# Sheet1.net
KiCad netlist of a schematic drawn in Altium Designer
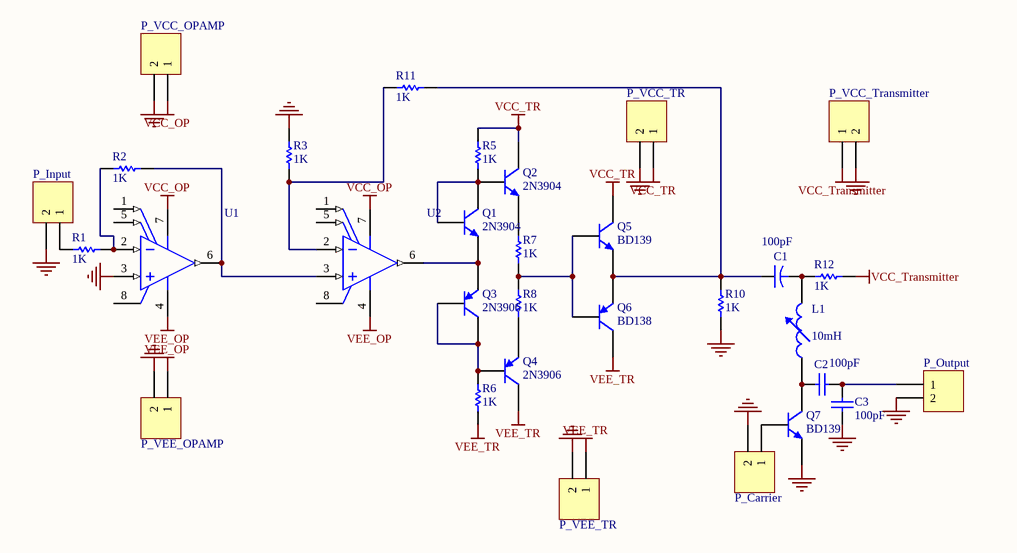
[diagram p0: Sheet1.SchDoc]

(export (version "E")
  (design (tool "Eeschema 10.0.6"))
  (components
    (comp (ref "C1")
      (value "100pF")
      (footprint "CAPR5-4X5")
      (description "Capacitor")
      (fields (field (name "Comment") "Cap2") (field (name "PUBLISHER") "Altium Limited"))
      (libsource (lib "Miscellaneous Devices") (part "Cap2"))
    )
    (comp (ref "C2")
      (value "100pF")
      (footprint "RAD-0.3")
      (description "Capacitor")
      (fields (field (name "Comment") "Cap") (field (name "PUBLISHER") "Altium Limited"))
      (libsource (lib "Miscellaneous Devices") (part "Cap"))
    )
    (comp (ref "C3")
      (value "100pF")
      (footprint "RAD-0.3")
      (description "Capacitor")
      (fields (field (name "Comment") "Cap") (field (name "PUBLISHER") "Altium Limited"))
      (libsource (lib "Miscellaneous Devices") (part "Cap"))
    )
    (comp (ref "L1")
      (value "10mH")
      (footprint "AXIAL-0.8")
      (description "Adjustable Inductor")
      (fields (field (name "Comment") "Inductor Adj") (field (name "PUBLISHER") "Altium Limited"))
      (libsource (lib "Miscellaneous Devices") (part "Inductor Adj"))
    )
    (comp (ref "P_Carrier")
      (value "Header 2")
      (footprint "HDR1X2")
      (description "Header, 2-Pin")
      (fields (field (name "PUBLISHER") "Altium Limited"))
      (libsource (lib "") (part "Header 2_1"))
    )
    (comp (ref "P_Input")
      (value "Header 2")
      (footprint "HDR1X2")
      (description "Header, 2-Pin")
      (fields (field (name "PUBLISHER") "Altium Limited"))
      (libsource (lib "Miscellaneous Connectors") (part "Header 2"))
    )
    (comp (ref "P_Output")
      (value "Header 2")
      (footprint "HDR1X2")
      (description "Header, 2-Pin")
      (fields (field (name "PUBLISHER") "Altium Limited"))
      (libsource (lib "Miscellaneous Connectors") (part "Header 2"))
    )
    (comp (ref "P_VCC_OPAMP")
      (value "Header 2")
      (footprint "HDR1X2")
      (description "Header, 2-Pin")
      (fields (field (name "PUBLISHER") "Altium Limited"))
      (libsource (lib "Miscellaneous Connectors") (part "Header 2"))
    )
    (comp (ref "P_VCC_TR")
      (value "Header 2")
      (footprint "HDR1X2")
      (description "Header, 2-Pin")
      (fields (field (name "PUBLISHER") "Altium Limited"))
      (libsource (lib "Miscellaneous Connectors") (part "Header 2"))
    )
    (comp (ref "P_VCC_Transmitter")
      (value "Header 2")
      (footprint "HDR1X2")
      (description "Header, 2-Pin")
      (fields (field (name "PUBLISHER") "Altium Limited"))
      (libsource (lib "") (part "Header 2_2"))
    )
    (comp (ref "P_VEE_OPAMP")
      (value "Header 2")
      (footprint "HDR1X2")
      (description "Header, 2-Pin")
      (fields (field (name "PUBLISHER") "Altium Limited"))
      (libsource (lib "") (part "Header 2_1"))
    )
    (comp (ref "P_VEE_TR")
      (value "Header 2")
      (footprint "HDR1X2")
      (description "Header, 2-Pin")
      (fields (field (name "PUBLISHER") "Altium Limited"))
      (libsource (lib "") (part "Header 2_1"))
    )
    (comp (ref "Q1")
      (value "2N3904")
      (footprint "TO-92A")
      (description "NPN General Purpose Amplifier")
      (fields (field (name "PUBLISHER") "Altium Limited"))
      (libsource (lib "Miscellaneous Devices") (part "2N3904"))
    )
    (comp (ref "Q2")
      (value "2N3904")
      (footprint "TO-92A")
      (description "NPN General Purpose Amplifier")
      (fields (field (name "PUBLISHER") "Altium Limited"))
      (libsource (lib "Miscellaneous Devices") (part "2N3904"))
    )
    (comp (ref "Q3")
      (value "2N3906")
      (footprint "TO-92A")
      (description "PNP General Purpose Amplifier")
      (fields (field (name "PUBLISHER") "Altium Limited"))
      (libsource (lib "Miscellaneous Devices") (part "2N3906"))
    )
    (comp (ref "Q4")
      (value "2N3906")
      (footprint "TO-92A")
      (description "PNP General Purpose Amplifier")
      (fields (field (name "PUBLISHER") "Altium Limited"))
      (libsource (lib "Miscellaneous Devices") (part "2N3906"))
    )
    (comp (ref "Q5")
      (value "BD139")
      (footprint "SOT-32")
      (description "NPN Transistor")
      (fields (field (name "E-MAIL") "picpars@gmail.com"))
      (libsource (lib "usefully_Library") (part "BD139"))
    )
    (comp (ref "Q6")
      (value "BD138")
      (footprint "SOT-32")
      (description "PNP Transistor")
      (fields (field (name "E-MAIL") "picpars@gmail.com"))
      (libsource (lib "usefully_Library") (part "BD138"))
    )
    (comp (ref "Q7")
      (value "BD139")
      (footprint "SOT-32")
      (description "NPN Transistor")
      (fields (field (name "E-MAIL") "picpars@gmail.com"))
      (libsource (lib "usefully_Library") (part "BD139"))
    )
    (comp (ref "R1")
      (value "1K")
      (footprint "AXIAL-0.3")
      (description "Resistor")
      (fields (field (name "Comment") "Res1") (field (name "PUBLISHER") "Altium Limited"))
      (libsource (lib "Miscellaneous Devices") (part "Res1"))
    )
    (comp (ref "R2")
      (value "1K")
      (footprint "AXIAL-0.3")
      (description "Resistor")
      (fields (field (name "Comment") "Res1") (field (name "PUBLISHER") "Altium Limited"))
      (libsource (lib "Miscellaneous Devices") (part "Res1"))
    )
    (comp (ref "R3")
      (value "1K")
      (footprint "AXIAL-0.3")
      (description "Resistor")
      (fields (field (name "Comment") "Res1") (field (name "PUBLISHER") "Altium Limited"))
      (libsource (lib "Miscellaneous Devices") (part "Res1"))
    )
    (comp (ref "R5")
      (value "1K")
      (footprint "AXIAL-0.3")
      (description "Resistor")
      (fields (field (name "Comment") "Res1") (field (name "PUBLISHER") "Altium Limited"))
      (libsource (lib "Miscellaneous Devices") (part "Res1"))
    )
    (comp (ref "R6")
      (value "1K")
      (footprint "AXIAL-0.3")
      (description "Resistor")
      (fields (field (name "Comment") "Res1") (field (name "PUBLISHER") "Altium Limited"))
      (libsource (lib "Miscellaneous Devices") (part "Res1"))
    )
    (comp (ref "R7")
      (value "1K")
      (footprint "AXIAL-0.3")
      (description "Resistor")
      (fields (field (name "Comment") "Res1") (field (name "PUBLISHER") "Altium Limited"))
      (libsource (lib "Miscellaneous Devices") (part "Res1"))
    )
    (comp (ref "R8")
      (value "1K")
      (footprint "AXIAL-0.3")
      (description "Resistor")
      (fields (field (name "Comment") "Res1") (field (name "PUBLISHER") "Altium Limited"))
      (libsource (lib "Miscellaneous Devices") (part "Res1"))
    )
    (comp (ref "R10")
      (value "1K")
      (footprint "AXIAL-0.3")
      (description "Resistor")
      (fields (field (name "Comment") "Res1") (field (name "PUBLISHER") "Altium Limited"))
      (libsource (lib "Miscellaneous Devices") (part "Res1"))
    )
    (comp (ref "R11")
      (value "1K")
      (footprint "AXIAL-0.3")
      (description "Resistor")
      (fields (field (name "Comment") "Res1") (field (name "PUBLISHER") "Altium Limited"))
      (libsource (lib "Miscellaneous Devices") (part "Res1"))
    )
    (comp (ref "R12")
      (value "1K")
      (footprint "AXIAL-0.3")
      (description "Resistor")
      (fields (field (name "Comment") "Res1") (field (name "PUBLISHER") "Altium Limited"))
      (libsource (lib "Miscellaneous Devices") (part "Res1"))
    )
    (comp (ref "U1")
      (value "UA741CP")
      (footprint "TI-P8")
      (description "General-Purpose Operational Amplifier, 7 to 36 V, 0 to 70 degC, 8-pin DIP (P8), Pb-Free (RoHS)")
      (fields (field (name "MANUFACTURER") "Texas Instruments"))
      (libsource (lib "TI_Amplifiers_and_Linear_Operational (2)") (part "UA741CP"))
    )
    (comp (ref "U2")
      (value "UA741CP")
      (footprint "TI-P8")
      (description "General-Purpose Operational Amplifier, 7 to 36 V, 0 to 70 degC, 8-pin DIP (P8), Pb-Free (RoHS)")
      (fields (field (name "MANUFACTURER") "Texas Instruments"))
      (libsource (lib "TI_Amplifiers_and_Linear_Operational (2)") (part "UA741CP"))
    )
  )
  (nets
    (net (code "1") (name "GND") (class "Default")
      (node (ref "C3") (pin "1") (pinfunction "1_1") (pintype "passive"))
      (node (ref "P_Carrier") (pin "2") (pinfunction "2_2") (pintype "passive"))
      (node (ref "P_Input") (pin "2") (pinfunction "2_2") (pintype "passive"))
      (node (ref "P_Output") (pin "2") (pinfunction "2_2") (pintype "passive"))
      (node (ref "P_VCC_OPAMP") (pin "2") (pinfunction "2_2") (pintype "passive"))
      (node (ref "P_VCC_TR") (pin "2") (pinfunction "2_2") (pintype "passive"))
      (node (ref "P_VCC_Transmitter") (pin "2") (pinfunction "2_2") (pintype "passive"))
      (node (ref "P_VEE_OPAMP") (pin "2") (pinfunction "2_2") (pintype "passive"))
      (node (ref "P_VEE_TR") (pin "2") (pinfunction "2_2") (pintype "passive"))
      (node (ref "Q7") (pin "E") (pinfunction "E_E") (pintype "passive"))
      (node (ref "R10") (pin "1") (pinfunction "1_1") (pintype "passive"))
      (node (ref "R3") (pin "2") (pinfunction "2_2") (pintype "passive"))
      (node (ref "U1") (pin "3") (pinfunction "IN+_3") (pintype "input"))
    )
    (net (code "2") (name "Net-(C1-Pad1)") (class "Default")
      (node (ref "C1") (pin "1") (pinfunction "1_1") (pintype "passive"))
      (node (ref "Q5") (pin "E") (pinfunction "E_E") (pintype "passive"))
      (node (ref "Q6") (pin "E") (pinfunction "E_E") (pintype "passive"))
      (node (ref "R10") (pin "2") (pinfunction "2_2") (pintype "passive"))
      (node (ref "R11") (pin "1") (pinfunction "1_1") (pintype "passive"))
    )
    (net (code "3") (name "Net-(C1-Pad2)") (class "Default")
      (node (ref "C1") (pin "2") (pinfunction "2_2") (pintype "passive"))
      (node (ref "L1") (pin "2") (pinfunction "2_2") (pintype "passive"))
      (node (ref "R12") (pin "2") (pinfunction "2_2") (pintype "passive"))
    )
    (net (code "4") (name "Net-(C2-Pad1)") (class "Default")
      (node (ref "C2") (pin "1") (pinfunction "1_1") (pintype "passive"))
      (node (ref "L1") (pin "1") (pinfunction "1_1") (pintype "passive"))
      (node (ref "Q7") (pin "C") (pinfunction "C_C") (pintype "passive"))
    )
    (net (code "5") (name "Net-(C2-Pad2)") (class "Default")
      (node (ref "C2") (pin "2") (pinfunction "2_2") (pintype "passive"))
      (node (ref "C3") (pin "2") (pinfunction "2_2") (pintype "passive"))
      (node (ref "P_Output") (pin "1") (pinfunction "1_1") (pintype "passive"))
    )
    (net (code "6") (name "Net-(P_Carrier-Pad1)") (class "Default")
      (node (ref "P_Carrier") (pin "1") (pinfunction "1_1") (pintype "passive"))
      (node (ref "Q7") (pin "B") (pinfunction "B_B") (pintype "passive"))
    )
    (net (code "7") (name "Net-(P_Input-Pad1)") (class "Default")
      (node (ref "P_Input") (pin "1") (pinfunction "1_1") (pintype "passive"))
      (node (ref "R1") (pin "2") (pinfunction "2_2") (pintype "passive"))
    )
    (net (code "8") (name "Net-(Q1-B)") (class "Default")
      (node (ref "Q1") (pin "2") (pinfunction "B_2") (pintype "passive"))
      (node (ref "Q1") (pin "3") (pinfunction "C_3") (pintype "passive"))
      (node (ref "Q2") (pin "2") (pinfunction "B_2") (pintype "passive"))
      (node (ref "R5") (pin "1") (pinfunction "1_1") (pintype "passive"))
    )
    (net (code "9") (name "Net-(Q1-E)") (class "Default")
      (node (ref "Q1") (pin "1") (pinfunction "E_1") (pintype "passive"))
      (node (ref "Q3") (pin "1") (pinfunction "E_1") (pintype "passive"))
      (node (ref "U2") (pin "6") (pinfunction "OUT_6") (pintype "output"))
    )
    (net (code "10") (name "Net-(Q2-E)") (class "Default")
      (node (ref "Q2") (pin "1") (pinfunction "E_1") (pintype "passive"))
      (node (ref "R7") (pin "2") (pinfunction "2_2") (pintype "passive"))
    )
    (net (code "11") (name "Net-(Q3-B)") (class "Default")
      (node (ref "Q3") (pin "2") (pinfunction "B_2") (pintype "passive"))
      (node (ref "Q3") (pin "3") (pinfunction "C_3") (pintype "passive"))
      (node (ref "Q4") (pin "2") (pinfunction "B_2") (pintype "passive"))
      (node (ref "R6") (pin "2") (pinfunction "2_2") (pintype "passive"))
    )
    (net (code "12") (name "Net-(Q4-E)") (class "Default")
      (node (ref "Q4") (pin "1") (pinfunction "E_1") (pintype "passive"))
      (node (ref "R8") (pin "1") (pinfunction "1_1") (pintype "passive"))
    )
    (net (code "13") (name "Net-(Q5-PadB)") (class "Default")
      (node (ref "Q5") (pin "B") (pinfunction "B_B") (pintype "passive"))
      (node (ref "Q6") (pin "B") (pinfunction "B_B") (pintype "passive"))
      (node (ref "R7") (pin "1") (pinfunction "1_1") (pintype "passive"))
      (node (ref "R8") (pin "2") (pinfunction "2_2") (pintype "passive"))
    )
    (net (code "14") (name "Net-(U1-IN-)") (class "Default")
      (node (ref "R1") (pin "1") (pinfunction "1_1") (pintype "passive"))
      (node (ref "R2") (pin "1") (pinfunction "1_1") (pintype "passive"))
      (node (ref "U1") (pin "2") (pinfunction "IN-_2") (pintype "input"))
    )
    (net (code "15") (name "Net-(U1-OUT)") (class "Default")
      (node (ref "R2") (pin "2") (pinfunction "2_2") (pintype "passive"))
      (node (ref "U1") (pin "6") (pinfunction "OUT_6") (pintype "output"))
      (node (ref "U2") (pin "3") (pinfunction "IN+_3") (pintype "input"))
    )
    (net (code "16") (name "Net-(U2-IN-)") (class "Default")
      (node (ref "R11") (pin "2") (pinfunction "2_2") (pintype "passive"))
      (node (ref "R3") (pin "1") (pinfunction "1_1") (pintype "passive"))
      (node (ref "U2") (pin "2") (pinfunction "IN-_2") (pintype "input"))
    )
    (net (code "17") (name "VCC_OP") (class "Default")
      (node (ref "P_VCC_OPAMP") (pin "1") (pinfunction "1_1") (pintype "passive"))
      (node (ref "U1") (pin "7") (pinfunction "VCC+_7") (pintype "power_in"))
      (node (ref "U2") (pin "7") (pinfunction "VCC+_7") (pintype "power_in"))
    )
    (net (code "18") (name "VCC_TR") (class "Default")
      (node (ref "P_VCC_TR") (pin "1") (pinfunction "1_1") (pintype "passive"))
      (node (ref "Q2") (pin "3") (pinfunction "C_3") (pintype "passive"))
      (node (ref "Q5") (pin "C") (pinfunction "C_C") (pintype "passive"))
      (node (ref "R5") (pin "2") (pinfunction "2_2") (pintype "passive"))
    )
    (net (code "19") (name "VCC_Transmitter") (class "Default")
      (node (ref "P_VCC_Transmitter") (pin "1") (pinfunction "1_1") (pintype "passive"))
      (node (ref "R12") (pin "1") (pinfunction "1_1") (pintype "passive"))
    )
    (net (code "20") (name "VEE_OP") (class "Default")
      (node (ref "P_VEE_OPAMP") (pin "1") (pinfunction "1_1") (pintype "passive"))
      (node (ref "U1") (pin "4") (pinfunction "VCC-_4") (pintype "power_in"))
      (node (ref "U2") (pin "4") (pinfunction "VCC-_4") (pintype "power_in"))
    )
    (net (code "21") (name "VEE_TR") (class "Default")
      (node (ref "P_VEE_TR") (pin "1") (pinfunction "1_1") (pintype "passive"))
      (node (ref "Q4") (pin "3") (pinfunction "C_3") (pintype "passive"))
      (node (ref "Q6") (pin "C") (pinfunction "C_C") (pintype "passive"))
      (node (ref "R6") (pin "1") (pinfunction "1_1") (pintype "passive"))
    )
    (net (code "22") (name "unconnected-(U1-NC-Pad8)") (class "Default")
      (node (ref "U1") (pin "8") (pinfunction "NC_8") (pintype "passive"))
    )
    (net (code "23") (name "unconnected-(U1-OFFSET_N1-Pad1)") (class "Default")
      (node (ref "U1") (pin "1") (pinfunction "OFFSET_N1_1") (pintype "input"))
    )
    (net (code "24") (name "unconnected-(U1-OFFSET_N2-Pad5)") (class "Default")
      (node (ref "U1") (pin "5") (pinfunction "OFFSET_N2_5") (pintype "input"))
    )
    (net (code "25") (name "unconnected-(U2-NC-Pad8)") (class "Default")
      (node (ref "U2") (pin "8") (pinfunction "NC_8") (pintype "passive"))
    )
    (net (code "26") (name "unconnected-(U2-OFFSET_N1-Pad1)") (class "Default")
      (node (ref "U2") (pin "1") (pinfunction "OFFSET_N1_1") (pintype "input"))
    )
    (net (code "27") (name "unconnected-(U2-OFFSET_N2-Pad5)") (class "Default")
      (node (ref "U2") (pin "5") (pinfunction "OFFSET_N2_5") (pintype "input"))
    )
  )
)
